# Sheet2.net
KiCad netlist of a schematic drawn in Altium Designer
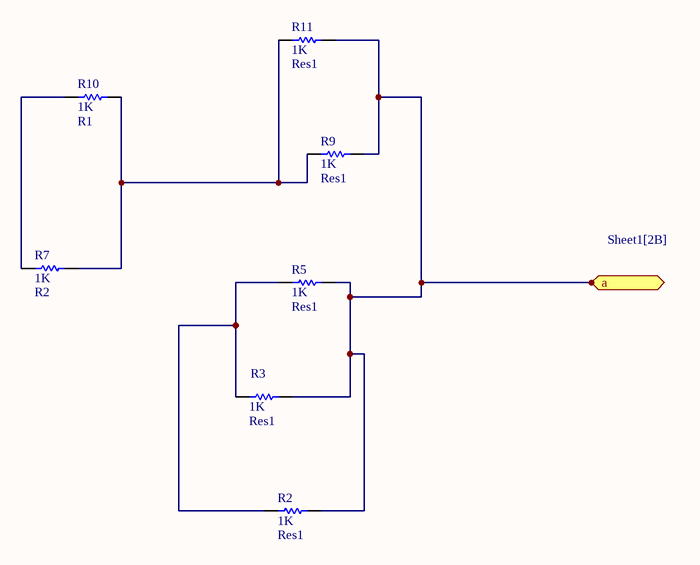
[diagram p0: Sheet2.SchDoc]

(export (version "E")
  (design (tool "Eeschema 10.0.6"))
  (components
    (comp (ref "R2")
      (value "Res1")
      (footprint "AXIAL-0.3")
      (description "Resistor")
      (fields (field (name "ALTIUM_VALUE") "1K") (field (name "PUBLISHER") "Altium Limited"))
      (libsource (lib "Miscellaneous Devices") (part "Res1"))
    )
    (comp (ref "R3")
      (value "Res1")
      (footprint "AXIAL-0.3")
      (description "Resistor")
      (fields (field (name "ALTIUM_VALUE") "1K") (field (name "PUBLISHER") "Altium Limited"))
      (libsource (lib "Miscellaneous Devices") (part "Res1"))
    )
    (comp (ref "R5")
      (value "Res1")
      (footprint "AXIAL-0.3")
      (description "Resistor")
      (fields (field (name "ALTIUM_VALUE") "1K") (field (name "PUBLISHER") "Altium Limited"))
      (libsource (lib "Miscellaneous Devices") (part "Res1"))
    )
    (comp (ref "R7")
      (value "R2")
      (footprint "AXIAL-0.3")
      (description "Resistor")
      (fields (field (name "ALTIUM_VALUE") "1K") (field (name "PUBLISHER") "Altium Limited"))
      (libsource (lib "Miscellaneous Devices") (part "Res1"))
    )
    (comp (ref "R9")
      (value "Res1")
      (footprint "AXIAL-0.3")
      (description "Resistor")
      (fields (field (name "ALTIUM_VALUE") "1K") (field (name "PUBLISHER") "Altium Limited"))
      (libsource (lib "Miscellaneous Devices") (part "Res1"))
    )
    (comp (ref "R10")
      (value "R1")
      (footprint "AXIAL-0.3")
      (description "Resistor")
      (fields (field (name "ALTIUM_VALUE") "1K") (field (name "PUBLISHER") "Altium Limited"))
      (libsource (lib "Miscellaneous Devices") (part "Res1"))
    )
    (comp (ref "R11")
      (value "Res1")
      (footprint "AXIAL-0.3")
      (description "Resistor")
      (fields (field (name "ALTIUM_VALUE") "1K") (field (name "PUBLISHER") "Altium Limited"))
      (libsource (lib "Miscellaneous Devices") (part "Res1"))
    )
  )
  (nets
    (net (code "1") (name "/a") (class "Default")
      (node (ref "R11") (pin "2") (pinfunction "2_2") (pintype "passive"))
      (node (ref "R2") (pin "2") (pinfunction "2_2") (pintype "passive"))
      (node (ref "R3") (pin "2") (pinfunction "2_2") (pintype "passive"))
      (node (ref "R5") (pin "2") (pinfunction "2_2") (pintype "passive"))
      (node (ref "R9") (pin "2") (pinfunction "2_2") (pintype "passive"))
    )
    (net (code "2") (name "Net-(R2-Pad1)") (class "Default")
      (node (ref "R2") (pin "1") (pinfunction "1_1") (pintype "passive"))
      (node (ref "R3") (pin "1") (pinfunction "1_1") (pintype "passive"))
      (node (ref "R5") (pin "1") (pinfunction "1_1") (pintype "passive"))
    )
    (net (code "3") (name "Net-(R10-Pad1)") (class "Default")
      (node (ref "R10") (pin "1") (pinfunction "1_1") (pintype "passive"))
      (node (ref "R7") (pin "1") (pinfunction "1_1") (pintype "passive"))
    )
    (net (code "4") (name "Net-(R10-Pad2)") (class "Default")
      (node (ref "R10") (pin "2") (pinfunction "2_2") (pintype "passive"))
      (node (ref "R11") (pin "1") (pinfunction "1_1") (pintype "passive"))
      (node (ref "R7") (pin "2") (pinfunction "2_2") (pintype "passive"))
      (node (ref "R9") (pin "1") (pinfunction "1_1") (pintype "passive"))
    )
  )
)
